# DM1098FFC_Connector.net
KiCad netlist of a schematic drawn in Altium Designer
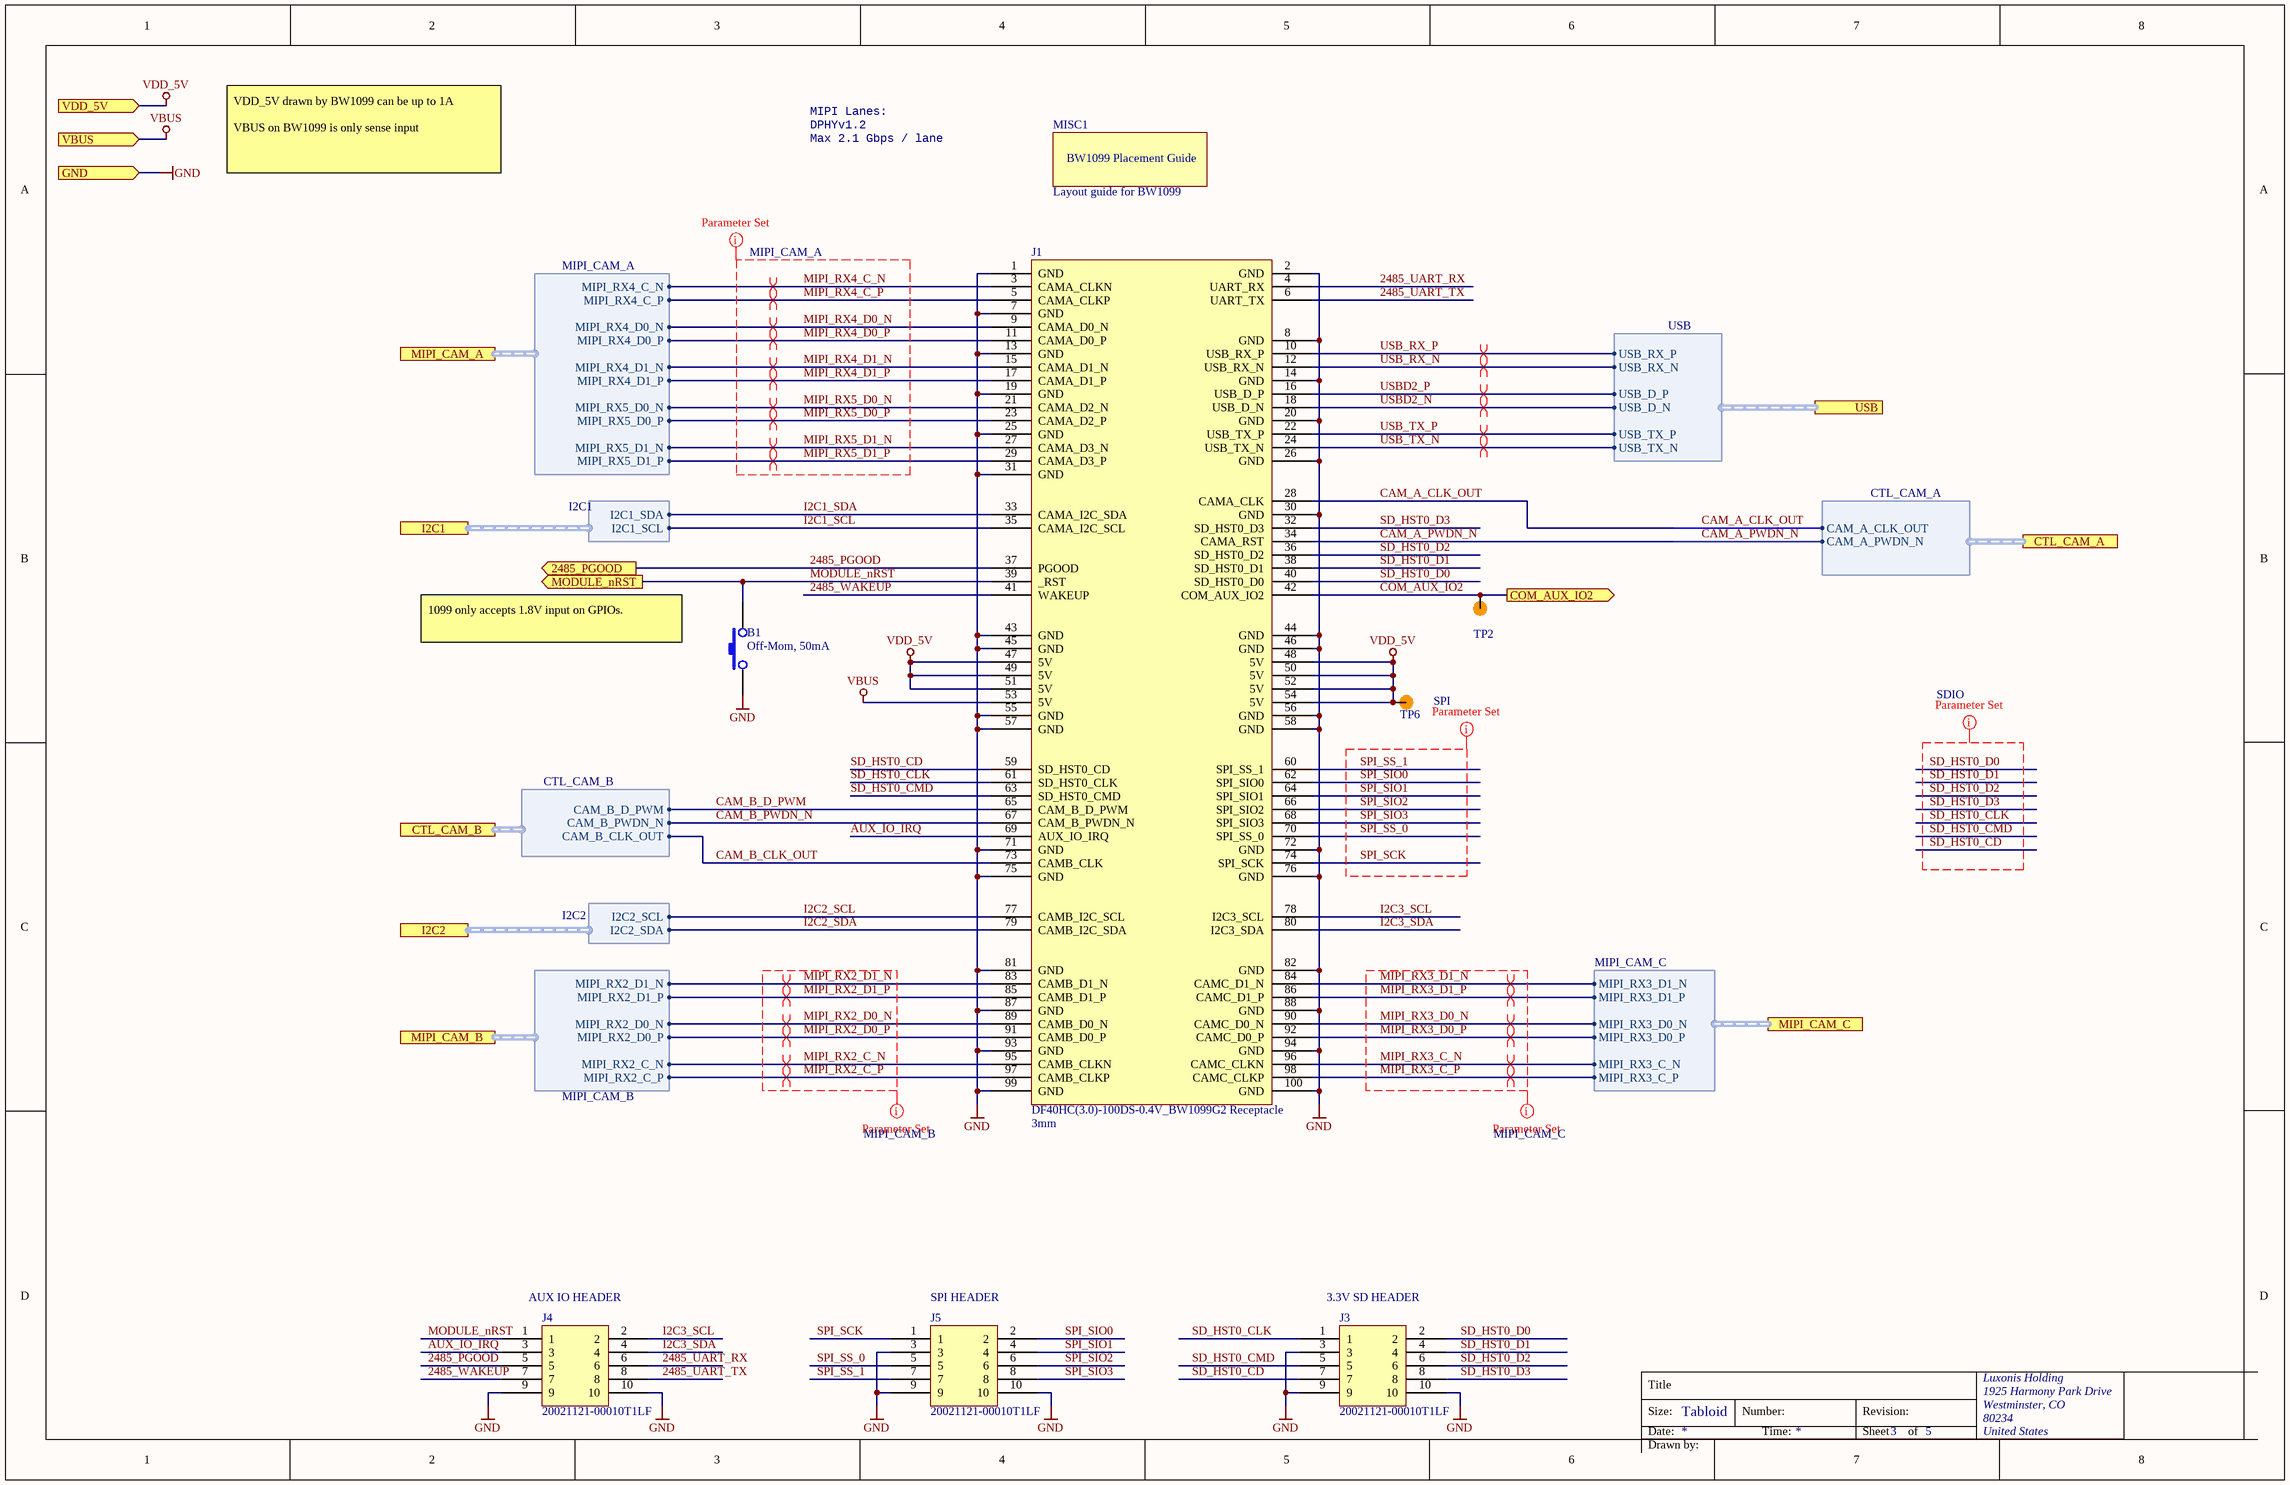
[diagram p0: DM1098FFC_Connector.SchDoc]

(export (version "E")
  (design (tool "Eeschema 10.0.6"))
  (components
    (comp (ref "B1")
      (value "Off-Mom, 50mA")
      (footprint "LuxonisMaster:DTSM-32N-V")
      (description "SWITCH TACTILE SMT 3.5mm * 6mm , brown 160gf")
      (libsource (lib "LuxonisMaster") (part "DTSM-32N-V"))
    )
    (comp (ref "J1")
      (value "DF40HC(3.0)-100DS-0.4V_BW1099G2 Receptacle")
      (footprint "LuxonisMaster:DF40HC-3.0-100DS-0.4V_minpad")
      (description "CONN RCPT 100POS 0.4MM SMD GOLD")
      (fields (field (name "MATED STACKING HEIGHT") "3mm"))
      (libsource (lib "LuxonisMaster") (part "DF40HC(3.0)-100DS-0.4V_BW1099_G2"))
    )
    (comp (ref "J3")
      (value "20021121-00010T1LF")
      (footprint "LuxonisMaster:20021121-00010T1LF")
      (description "CONN HEADER SMD 10POS 1.27MM")
      (libsource (lib "LuxonisMaster") (part "20021121-00010T1LF"))
    )
    (comp (ref "J4")
      (value "20021121-00010T1LF")
      (footprint "LuxonisMaster:20021121-00010T1LF")
      (description "CONN HEADER SMD 10POS 1.27MM")
      (libsource (lib "LuxonisMaster") (part "20021121-00010T1LF"))
    )
    (comp (ref "J5")
      (value "20021121-00010T1LF")
      (footprint "LuxonisMaster:20021121-00010T1LF")
      (description "CONN HEADER SMD 10POS 1.27MM")
      (libsource (lib "LuxonisMaster") (part "20021121-00010T1LF"))
    )
    (comp (ref "MISC1")
      (value "Layout guide for BW1099")
      (footprint "BW1099_R3_KTHSNF_Footprint")
      (description "MISC - Use for aligning BW1099 mount")
      (libsource (lib "LuxonisMaster") (part "BW1099_Footprint"))
    )
    (comp (ref "TP2")
      (value "TP100_200_NS")
      (footprint "LuxonisMaster:TP100_200_NS")
      (libsource (lib "LuxonisMaster") (part "TEST_POINT"))
    )
    (comp (ref "TP6")
      (value "TP100_200_NS")
      (footprint "LuxonisMaster:TP100_200_NS")
      (libsource (lib "LuxonisMaster") (part "TEST_POINT"))
    )
  )
  (nets
    (net (code "9") (name "/2485_PGOOD") (class "Default")
      (node (ref "J1") (pin "37") (pinfunction "PGOOD_37") (pintype "passive"))
      (node (ref "J4") (pin "5") (pinfunction "5_5") (pintype "passive"))
    )
    (net (code "10") (name "/2485_UART_RX") (class "Default")
      (node (ref "J1") (pin "4") (pinfunction "UART_RX_4") (pintype "passive"))
      (node (ref "J4") (pin "6") (pinfunction "6_6") (pintype "passive"))
    )
    (net (code "11") (name "/2485_UART_TX") (class "Default")
      (node (ref "J1") (pin "6") (pinfunction "UART_TX_6") (pintype "passive"))
      (node (ref "J4") (pin "8") (pinfunction "8_8") (pintype "passive"))
    )
    (net (code "12") (name "/2485_WAKEUP") (class "Default")
      (node (ref "J1") (pin "41") (pinfunction "WAKEUP_41") (pintype "passive"))
      (node (ref "J4") (pin "7") (pinfunction "7_7") (pintype "passive"))
    )
    (net (code "13") (name "/AUX_IO_IRQ") (class "Default")
      (node (ref "J1") (pin "69") (pinfunction "AUX_IO_IRQ_69") (pintype "passive"))
      (node (ref "J4") (pin "3") (pinfunction "3_3") (pintype "passive"))
    )
    (net (code "14") (name "/CAM_A_CLK_OUT") (class "Default")
      (node (ref "J1") (pin "28") (pinfunction "CAMA_CLK_28") (pintype "passive"))
    )
    (net (code "15") (name "/CAM_A_PWDN_N") (class "Default")
      (node (ref "J1") (pin "34") (pinfunction "CAMA_RST_34") (pintype "passive"))
    )
    (net (code "16") (name "/CAM_B_CLK_OUT") (class "Default")
      (node (ref "J1") (pin "73") (pinfunction "CAMB_CLK_73") (pintype "passive"))
    )
    (net (code "17") (name "/CAM_B_D_PWM") (class "Default")
      (node (ref "J1") (pin "65") (pinfunction "CAM_B_D_PWM_65") (pintype "passive"))
    )
    (net (code "18") (name "/CAM_B_PWDN_N") (class "Default")
      (node (ref "J1") (pin "67") (pinfunction "CAM_B_PWDN_N_67") (pintype "passive"))
    )
    (net (code "19") (name "/COM_AUX_IO2") (class "Default")
      (node (ref "J1") (pin "42") (pinfunction "COM_AUX_IO2_42") (pintype "passive"))
      (node (ref "TP2") (pin "1") (pintype "passive"))
    )
    (net (code "20") (name "/I2C1_SCL") (class "Default")
      (node (ref "J1") (pin "35") (pinfunction "CAMA_I2C_SCL_35") (pintype "passive"))
    )
    (net (code "21") (name "/I2C1_SDA") (class "Default")
      (node (ref "J1") (pin "33") (pinfunction "CAMA_I2C_SDA_33") (pintype "passive"))
    )
    (net (code "22") (name "/I2C2_SCL") (class "Default")
      (node (ref "J1") (pin "77") (pinfunction "CAMB_I2C_SCL_77") (pintype "passive"))
    )
    (net (code "23") (name "/I2C2_SDA") (class "Default")
      (node (ref "J1") (pin "79") (pinfunction "CAMB_I2C_SDA_79") (pintype "passive"))
    )
    (net (code "24") (name "/I2C3_SCL") (class "Default")
      (node (ref "J1") (pin "78") (pinfunction "I2C3_SCL_78") (pintype "passive"))
      (node (ref "J4") (pin "2") (pinfunction "2_2") (pintype "passive"))
    )
    (net (code "25") (name "/I2C3_SDA") (class "Default")
      (node (ref "J1") (pin "80") (pinfunction "I2C3_SDA_80") (pintype "passive"))
      (node (ref "J4") (pin "4") (pinfunction "4_4") (pintype "passive"))
    )
    (net (code "26") (name "/MIPI_RX2_C_N") (class "Default")
      (node (ref "J1") (pin "95") (pinfunction "CAMB_CLKN_95") (pintype "passive"))
    )
    (net (code "27") (name "/MIPI_RX2_C_P") (class "Default")
      (node (ref "J1") (pin "97") (pinfunction "CAMB_CLKP_97") (pintype "passive"))
    )
    (net (code "28") (name "/MIPI_RX2_D0_N") (class "Default")
      (node (ref "J1") (pin "89") (pinfunction "CAMB_D0_N_89") (pintype "passive"))
    )
    (net (code "29") (name "/MIPI_RX2_D0_P") (class "Default")
      (node (ref "J1") (pin "91") (pinfunction "CAMB_D0_P_91") (pintype "passive"))
    )
    (net (code "30") (name "/MIPI_RX2_D1_N") (class "Default")
      (node (ref "J1") (pin "83") (pinfunction "CAMB_D1_N_83") (pintype "passive"))
    )
    (net (code "31") (name "/MIPI_RX2_D1_P") (class "Default")
      (node (ref "J1") (pin "85") (pinfunction "CAMB_D1_P_85") (pintype "passive"))
    )
    (net (code "32") (name "/MIPI_RX3_C_N") (class "Default")
      (node (ref "J1") (pin "96") (pinfunction "CAMC_CLKN_96") (pintype "passive"))
    )
    (net (code "33") (name "/MIPI_RX3_C_P") (class "Default")
      (node (ref "J1") (pin "98") (pinfunction "CAMC_CLKP_98") (pintype "passive"))
    )
    (net (code "34") (name "/MIPI_RX3_D0_N") (class "Default")
      (node (ref "J1") (pin "90") (pinfunction "CAMC_D0_N_90") (pintype "passive"))
    )
    (net (code "35") (name "/MIPI_RX3_D0_P") (class "Default")
      (node (ref "J1") (pin "92") (pinfunction "CAMC_D0_P_92") (pintype "passive"))
    )
    (net (code "36") (name "/MIPI_RX3_D1_N") (class "Default")
      (node (ref "J1") (pin "84") (pinfunction "CAMC_D1_N_84") (pintype "passive"))
    )
    (net (code "37") (name "/MIPI_RX3_D1_P") (class "Default")
      (node (ref "J1") (pin "86") (pinfunction "CAMC_D1_P_86") (pintype "passive"))
    )
    (net (code "38") (name "/MIPI_RX4_C_N") (class "Default")
      (node (ref "J1") (pin "3") (pinfunction "CAMA_CLKN_3") (pintype "passive"))
    )
    (net (code "39") (name "/MIPI_RX4_C_P") (class "Default")
      (node (ref "J1") (pin "5") (pinfunction "CAMA_CLKP_5") (pintype "passive"))
    )
    (net (code "40") (name "/MIPI_RX4_D0_N") (class "Default")
      (node (ref "J1") (pin "9") (pinfunction "CAMA_D0_N_9") (pintype "passive"))
    )
    (net (code "41") (name "/MIPI_RX4_D0_P") (class "Default")
      (node (ref "J1") (pin "11") (pinfunction "CAMA_D0_P_11") (pintype "passive"))
    )
    (net (code "42") (name "/MIPI_RX4_D1_N") (class "Default")
      (node (ref "J1") (pin "15") (pinfunction "CAMA_D1_N_15") (pintype "passive"))
    )
    (net (code "43") (name "/MIPI_RX4_D1_P") (class "Default")
      (node (ref "J1") (pin "17") (pinfunction "CAMA_D1_P_17") (pintype "passive"))
    )
    (net (code "44") (name "/MIPI_RX5_D0_N") (class "Default")
      (node (ref "J1") (pin "21") (pinfunction "CAMA_D2_N_21") (pintype "passive"))
    )
    (net (code "45") (name "/MIPI_RX5_D0_P") (class "Default")
      (node (ref "J1") (pin "23") (pinfunction "CAMA_D2_P_23") (pintype "passive"))
    )
    (net (code "46") (name "/MIPI_RX5_D1_N") (class "Default")
      (node (ref "J1") (pin "27") (pinfunction "CAMA_D3_N_27") (pintype "passive"))
    )
    (net (code "47") (name "/MIPI_RX5_D1_P") (class "Default")
      (node (ref "J1") (pin "29") (pinfunction "CAMA_D3_P_29") (pintype "passive"))
    )
    (net (code "48") (name "/MODULE_nRST") (class "Default")
      (node (ref "B1") (pin "2") (pinfunction "2_2") (pintype "passive"))
      (node (ref "J1") (pin "39") (pinfunction "_RST_39") (pintype "passive"))
      (node (ref "J4") (pin "1") (pinfunction "1_1") (pintype "passive"))
    )
    (net (code "49") (name "/SD_HST0_CD") (class "Default")
      (node (ref "J1") (pin "59") (pinfunction "SD_HST0_CD_59") (pintype "passive"))
      (node (ref "J3") (pin "7") (pinfunction "7_7") (pintype "passive"))
    )
    (net (code "50") (name "/SD_HST0_CLK") (class "Default")
      (node (ref "J1") (pin "61") (pinfunction "SD_HST0_CLK_61") (pintype "passive"))
      (node (ref "J3") (pin "1") (pinfunction "1_1") (pintype "passive"))
    )
    (net (code "51") (name "/SD_HST0_CMD") (class "Default")
      (node (ref "J1") (pin "63") (pinfunction "SD_HST0_CMD_63") (pintype "passive"))
      (node (ref "J3") (pin "5") (pinfunction "5_5") (pintype "passive"))
    )
    (net (code "52") (name "/SD_HST0_D0") (class "Default")
      (node (ref "J1") (pin "40") (pinfunction "SD_HST0_D0_40") (pintype "passive"))
      (node (ref "J3") (pin "2") (pinfunction "2_2") (pintype "passive"))
    )
    (net (code "53") (name "/SD_HST0_D1") (class "Default")
      (node (ref "J1") (pin "38") (pinfunction "SD_HST0_D1_38") (pintype "passive"))
      (node (ref "J3") (pin "4") (pinfunction "4_4") (pintype "passive"))
    )
    (net (code "54") (name "/SD_HST0_D2") (class "Default")
      (node (ref "J1") (pin "36") (pinfunction "SD_HST0_D2_36") (pintype "passive"))
      (node (ref "J3") (pin "6") (pinfunction "6_6") (pintype "passive"))
    )
    (net (code "55") (name "/SD_HST0_D3") (class "Default")
      (node (ref "J1") (pin "32") (pinfunction "SD_HST0_D3_32") (pintype "passive"))
      (node (ref "J3") (pin "8") (pinfunction "8_8") (pintype "passive"))
    )
    (net (code "56") (name "/SPI_SCK") (class "Default")
      (node (ref "J1") (pin "74") (pinfunction "SPI_SCK_74") (pintype "passive"))
      (node (ref "J5") (pin "1") (pinfunction "1_1") (pintype "passive"))
    )
    (net (code "57") (name "/SPI_SIO0") (class "Default")
      (node (ref "J1") (pin "62") (pinfunction "SPI_SIO0_62") (pintype "passive"))
      (node (ref "J5") (pin "2") (pinfunction "2_2") (pintype "passive"))
    )
    (net (code "58") (name "/SPI_SIO1") (class "Default")
      (node (ref "J1") (pin "64") (pinfunction "SPI_SIO1_64") (pintype "passive"))
      (node (ref "J5") (pin "4") (pinfunction "4_4") (pintype "passive"))
    )
    (net (code "59") (name "/SPI_SIO2") (class "Default")
      (node (ref "J1") (pin "66") (pinfunction "SPI_SIO2_66") (pintype "passive"))
      (node (ref "J5") (pin "6") (pinfunction "6_6") (pintype "passive"))
    )
    (net (code "60") (name "/SPI_SIO3") (class "Default")
      (node (ref "J1") (pin "68") (pinfunction "SPI_SIO3_68") (pintype "passive"))
      (node (ref "J5") (pin "8") (pinfunction "8_8") (pintype "passive"))
    )
    (net (code "61") (name "/SPI_SS_0") (class "Default")
      (node (ref "J1") (pin "70") (pinfunction "SPI_SS_0_70") (pintype "passive"))
      (node (ref "J5") (pin "5") (pinfunction "5_5") (pintype "passive"))
    )
    (net (code "62") (name "/SPI_SS_1") (class "Default")
      (node (ref "J1") (pin "60") (pinfunction "SPI_SS_1_60") (pintype "passive"))
      (node (ref "J5") (pin "7") (pinfunction "7_7") (pintype "passive"))
    )
    (net (code "63") (name "/USBD2_N") (class "Default")
      (node (ref "J1") (pin "18") (pinfunction "USB_D_N_18") (pintype "passive"))
    )
    (net (code "64") (name "/USBD2_P") (class "Default")
      (node (ref "J1") (pin "16") (pinfunction "USB_D_P_16") (pintype "passive"))
    )
    (net (code "65") (name "/USB_RX_N") (class "Default")
      (node (ref "J1") (pin "12") (pinfunction "USB_RX_N_12") (pintype "passive"))
    )
    (net (code "66") (name "/USB_RX_P") (class "Default")
      (node (ref "J1") (pin "10") (pinfunction "USB_RX_P_10") (pintype "passive"))
    )
    (net (code "67") (name "/USB_TX_N") (class "Default")
      (node (ref "J1") (pin "24") (pinfunction "USB_TX_N_24") (pintype "passive"))
    )
    (net (code "68") (name "/USB_TX_P") (class "Default")
      (node (ref "J1") (pin "22") (pinfunction "USB_TX_P_22") (pintype "passive"))
    )
    (net (code "77") (name "GND") (class "Default")
      (node (ref "B1") (pin "1") (pinfunction "1_1") (pintype "passive"))
      (node (ref "J1") (pin "1") (pinfunction "GND_1") (pintype "passive"))
      (node (ref "J1") (pin "100") (pinfunction "GND_100") (pintype "passive"))
      (node (ref "J1") (pin "13") (pinfunction "GND_13") (pintype "passive"))
      (node (ref "J1") (pin "14") (pinfunction "GND_14") (pintype "passive"))
      (node (ref "J1") (pin "19") (pinfunction "GND_19") (pintype "passive"))
      (node (ref "J1") (pin "2") (pinfunction "GND_2") (pintype "passive"))
      (node (ref "J1") (pin "20") (pinfunction "GND_20") (pintype "passive"))
      (node (ref "J1") (pin "25") (pinfunction "GND_25") (pintype "passive"))
      (node (ref "J1") (pin "26") (pinfunction "GND_26") (pintype "passive"))
      (node (ref "J1") (pin "30") (pinfunction "GND_30") (pintype "passive"))
      (node (ref "J1") (pin "31") (pinfunction "GND_31") (pintype "passive"))
      (node (ref "J1") (pin "43") (pinfunction "GND_43") (pintype "passive"))
      (node (ref "J1") (pin "44") (pinfunction "GND_44") (pintype "passive"))
      (node (ref "J1") (pin "45") (pinfunction "GND_45") (pintype "passive"))
      (node (ref "J1") (pin "46") (pinfunction "GND_46") (pintype "passive"))
      (node (ref "J1") (pin "55") (pinfunction "GND_55") (pintype "passive"))
      (node (ref "J1") (pin "56") (pinfunction "GND_56") (pintype "passive"))
      (node (ref "J1") (pin "57") (pinfunction "GND_57") (pintype "passive"))
      (node (ref "J1") (pin "58") (pinfunction "GND_58") (pintype "passive"))
      (node (ref "J1") (pin "7") (pinfunction "GND_7") (pintype "passive"))
      (node (ref "J1") (pin "71") (pinfunction "GND_71") (pintype "passive"))
      (node (ref "J1") (pin "72") (pinfunction "GND_72") (pintype "passive"))
      (node (ref "J1") (pin "75") (pinfunction "GND_75") (pintype "passive"))
      (node (ref "J1") (pin "76") (pinfunction "GND_76") (pintype "passive"))
      (node (ref "J1") (pin "8") (pinfunction "GND_8") (pintype "passive"))
      (node (ref "J1") (pin "81") (pinfunction "GND_81") (pintype "passive"))
      (node (ref "J1") (pin "82") (pinfunction "GND_82") (pintype "passive"))
      (node (ref "J1") (pin "87") (pinfunction "GND_87") (pintype "passive"))
      (node (ref "J1") (pin "88") (pinfunction "GND_88") (pintype "passive"))
      (node (ref "J1") (pin "93") (pinfunction "GND_93") (pintype "passive"))
      (node (ref "J1") (pin "94") (pinfunction "GND_94") (pintype "passive"))
      (node (ref "J1") (pin "99") (pinfunction "GND_99") (pintype "passive"))
      (node (ref "J3") (pin "10") (pinfunction "10_10") (pintype "passive"))
      (node (ref "J3") (pin "3") (pinfunction "3_3") (pintype "passive"))
      (node (ref "J3") (pin "9") (pinfunction "9_9") (pintype "passive"))
      (node (ref "J4") (pin "10") (pinfunction "10_10") (pintype "passive"))
      (node (ref "J4") (pin "9") (pinfunction "9_9") (pintype "passive"))
      (node (ref "J5") (pin "10") (pinfunction "10_10") (pintype "passive"))
      (node (ref "J5") (pin "3") (pinfunction "3_3") (pintype "passive"))
      (node (ref "J5") (pin "9") (pinfunction "9_9") (pintype "passive"))
    )
    (net (code "78") (name "VBUS") (class "Default")
      (node (ref "J1") (pin "53") (pinfunction "5V_53") (pintype "passive"))
    )
    (net (code "79") (name "VDD_5V") (class "Default")
      (node (ref "J1") (pin "47") (pinfunction "5V_47") (pintype "passive"))
      (node (ref "J1") (pin "48") (pinfunction "5V_48") (pintype "passive"))
      (node (ref "J1") (pin "49") (pinfunction "5V_49") (pintype "passive"))
      (node (ref "J1") (pin "50") (pinfunction "5V_50") (pintype "passive"))
      (node (ref "J1") (pin "51") (pinfunction "5V_51") (pintype "passive"))
      (node (ref "J1") (pin "52") (pinfunction "5V_52") (pintype "passive"))
      (node (ref "J1") (pin "54") (pinfunction "5V_54") (pintype "passive"))
      (node (ref "TP6") (pin "1") (pintype "passive"))
    )
  )
)
